# expansion_board.net
KiCad netlist of a schematic drawn in EAGLE
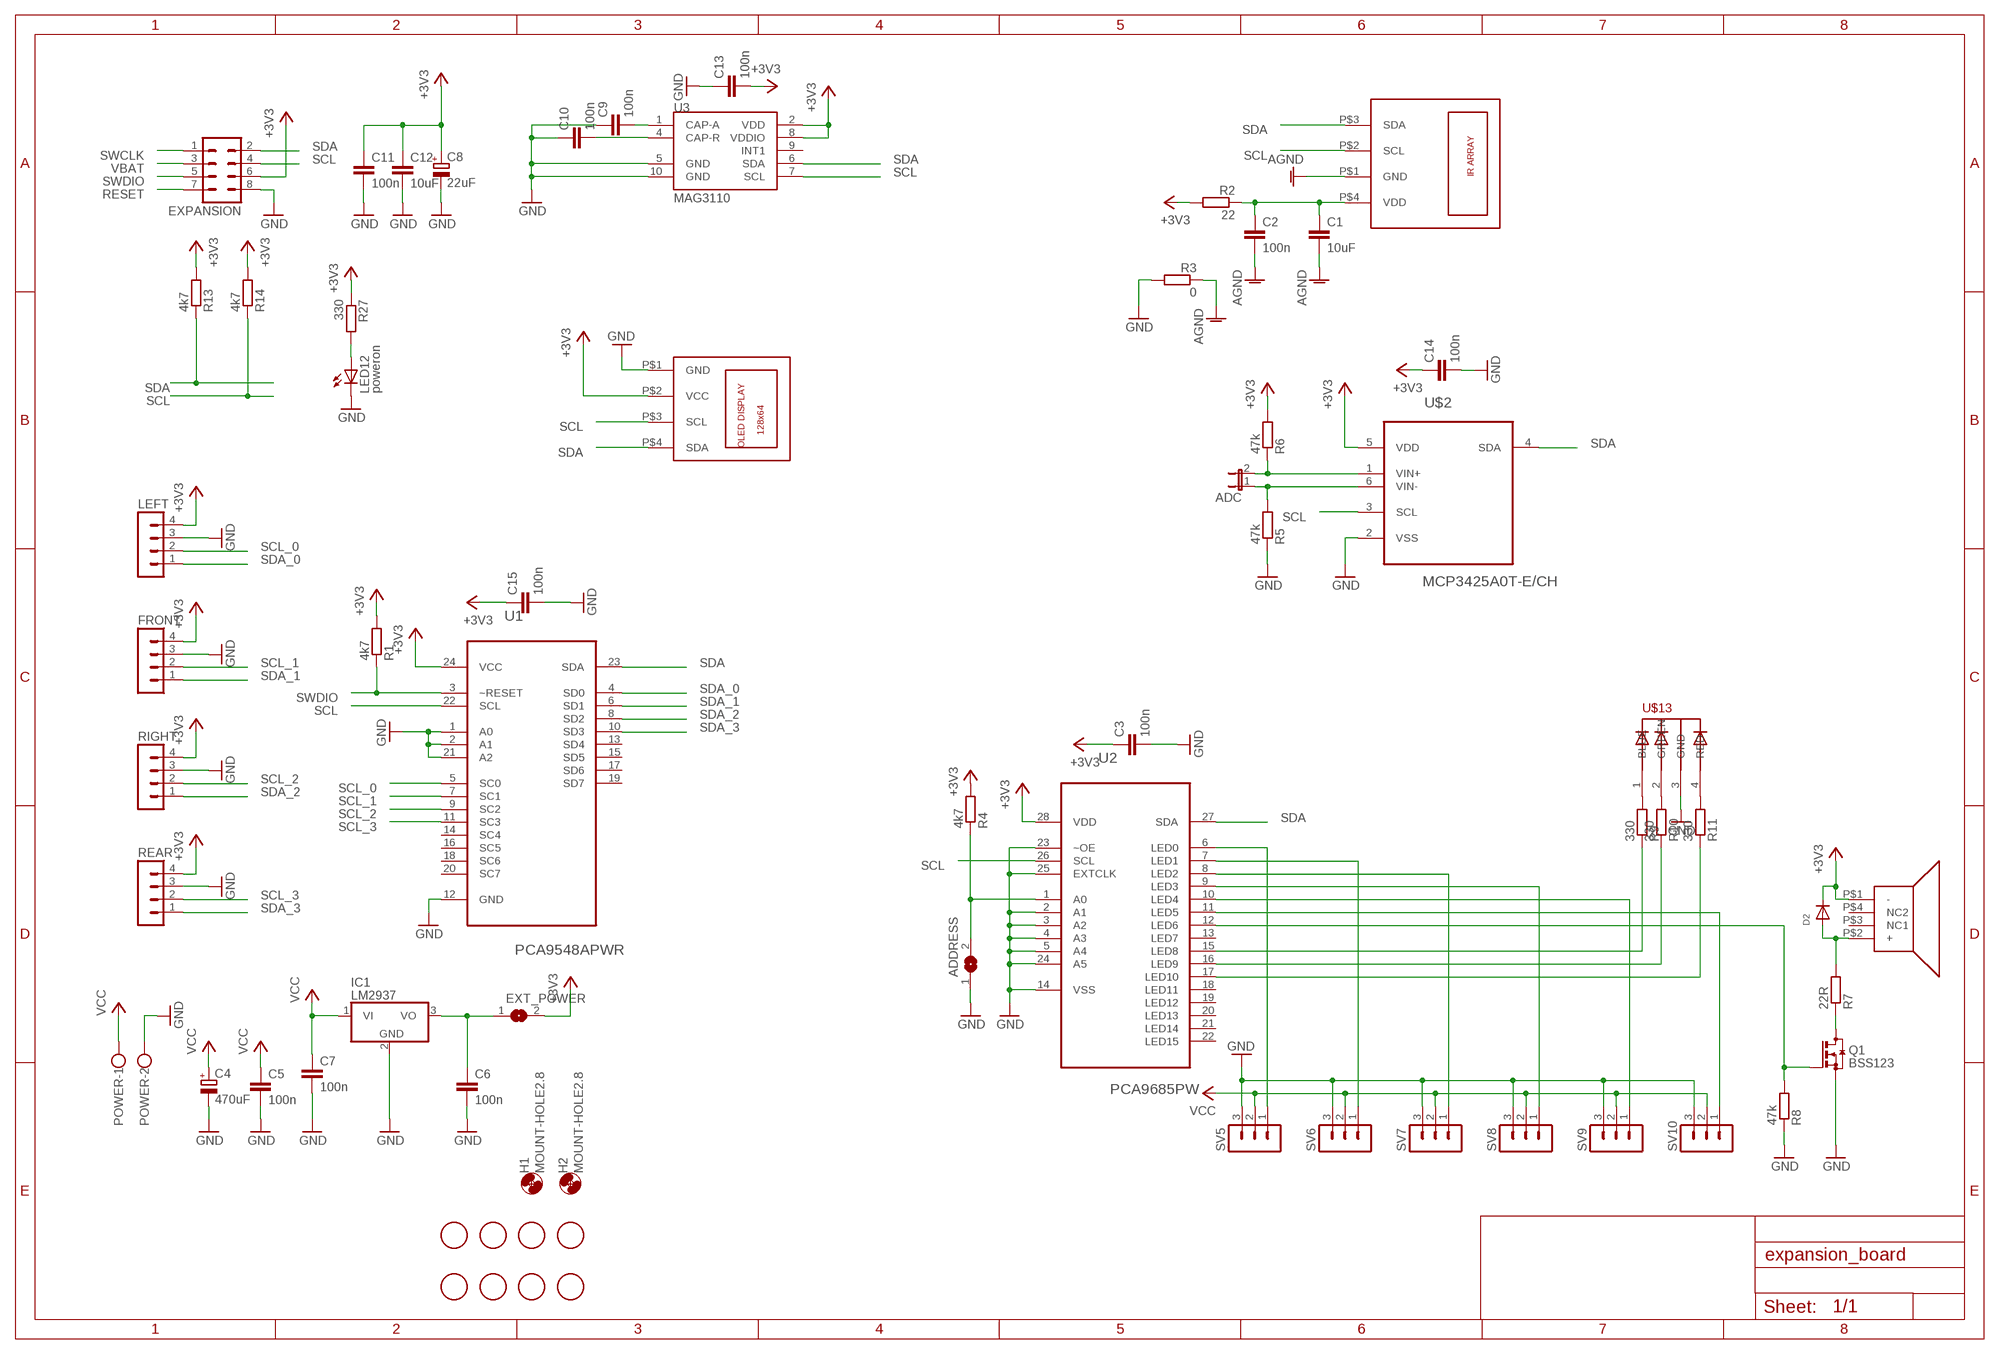
[diagram p0: schematic, sheet 1]

(export (version "E")
  (design (tool "Eeschema 10.0.6"))
  (components
    (comp (ref "ADC")
      (value "JP1E")
      (footprint "eagle-import:JP1")
      (libsource (lib "eagle-import") (part "JP1E"))
    )
    (comp (ref "ADDRESS")
      (value "SJ")
      (footprint "eagle-import:SJ")
      (libsource (lib "eagle-import") (part "SJ"))
    )
    (comp (ref "C1")
      (value "10uF")
      (footprint "eagle-import:C0805")
      (libsource (lib "eagle-import") (part "C-EUC0805"))
    )
    (comp (ref "C2")
      (value "100n")
      (footprint "eagle-import:C0805")
      (libsource (lib "eagle-import") (part "C-EUC0805"))
    )
    (comp (ref "C3")
      (value "100n")
      (footprint "eagle-import:C0805")
      (libsource (lib "eagle-import") (part "C-EUC0805"))
    )
    (comp (ref "C4")
      (value "470uF")
      (footprint "eagle-import:153CLV-1012")
      (libsource (lib "eagle-import") (part "CPOL-EU153CLV-1012"))
    )
    (comp (ref "C5")
      (value "100n")
      (footprint "eagle-import:C0805")
      (libsource (lib "eagle-import") (part "C-EUC0805"))
    )
    (comp (ref "C6")
      (value "100n")
      (footprint "eagle-import:C0805")
      (libsource (lib "eagle-import") (part "C-EUC0805"))
    )
    (comp (ref "C7")
      (value "100n")
      (footprint "eagle-import:C0805")
      (libsource (lib "eagle-import") (part "C-EUC0805"))
    )
    (comp (ref "C8")
      (value "22uF")
      (footprint "eagle-import:153CLV-0505")
      (libsource (lib "eagle-import") (part "CPOL-EU153CLV-0505"))
    )
    (comp (ref "C9")
      (value "100n")
      (footprint "eagle-import:C0805")
      (libsource (lib "eagle-import") (part "C-EUC0805"))
    )
    (comp (ref "C10")
      (value "100n")
      (footprint "eagle-import:C0805")
      (libsource (lib "eagle-import") (part "C-EUC0805"))
    )
    (comp (ref "C11")
      (value "100n")
      (footprint "eagle-import:C0805")
      (libsource (lib "eagle-import") (part "C-EUC0805"))
    )
    (comp (ref "C12")
      (value "10uF")
      (footprint "eagle-import:C0805")
      (libsource (lib "eagle-import") (part "C-EUC0805"))
    )
    (comp (ref "C13")
      (value "100n")
      (footprint "eagle-import:C0805")
      (libsource (lib "eagle-import") (part "C-EUC0805"))
    )
    (comp (ref "C14")
      (value "100n")
      (footprint "eagle-import:C0805")
      (libsource (lib "eagle-import") (part "C-EUC0805"))
    )
    (comp (ref "C15")
      (value "100n")
      (footprint "eagle-import:C0805")
      (libsource (lib "eagle-import") (part "C-EUC0805"))
    )
    (comp (ref "D2")
      (value "DIODE_SOD-123FL")
      (footprint "eagle-import:SOD-123FL")
      (libsource (lib "eagle-import") (part "DIODE_SOD-123FL"))
    )
    (comp (ref "EXPANSION")
      (value "MA04-2")
      (footprint "eagle-import:MA04-2")
      (libsource (lib "eagle-import") (part "MA04-2"))
    )
    (comp (ref "EXT_POWER")
      (value "SJ")
      (footprint "eagle-import:SJ")
      (libsource (lib "eagle-import") (part "SJ"))
    )
    (comp (ref "FRONT")
      (value "MA04-1")
      (footprint "eagle-import:MA04-1")
      (libsource (lib "eagle-import") (part "MA04-1"))
    )
    (comp (ref "H1")
      (value "MOUNT-HOLE2.8")
      (footprint "eagle-import:2,8")
      (libsource (lib "eagle-import") (part "MOUNT-HOLE2.8"))
    )
    (comp (ref "H2")
      (value "MOUNT-HOLE2.8")
      (footprint "eagle-import:2,8")
      (libsource (lib "eagle-import") (part "MOUNT-HOLE2.8"))
    )
    (comp (ref "IC1")
      (value "LM2937")
      (footprint "eagle-import:TO263-3")
      (libsource (lib "eagle-import") (part "LM2937"))
    )
    (comp (ref "LED12")
      (value "poweron")
      (footprint "eagle-import:CHIPLED_1206")
      (libsource (lib "eagle-import") (part "LEDCHIPLED_1206"))
    )
    (comp (ref "LEFT")
      (value "MA04-1")
      (footprint "eagle-import:MA04-1")
      (libsource (lib "eagle-import") (part "MA04-1"))
    )
    (comp (ref "POWER")
      (value "W237-102")
      (footprint "eagle-import:W237-102")
      (fields (field (name "MPN") "237-102"))
      (libsource (lib "eagle-import") (part "W237-102"))
    )
    (comp (ref "Q1")
      (value "BSS123")
      (footprint "eagle-import:SOT23")
      (libsource (lib "eagle-import") (part "BSS123"))
    )
    (comp (ref "R1")
      (value "4k7")
      (footprint "eagle-import:M0805")
      (libsource (lib "eagle-import") (part "R-EU_M0805"))
    )
    (comp (ref "R2")
      (value "22")
      (footprint "eagle-import:M0805")
      (libsource (lib "eagle-import") (part "R-EU_M0805"))
    )
    (comp (ref "R3")
      (value "0")
      (footprint "eagle-import:M0805")
      (libsource (lib "eagle-import") (part "R-EU_M0805"))
    )
    (comp (ref "R4")
      (value "4k7")
      (footprint "eagle-import:M0805")
      (libsource (lib "eagle-import") (part "R-EU_M0805"))
    )
    (comp (ref "R5")
      (value "47k")
      (footprint "eagle-import:M0805")
      (libsource (lib "eagle-import") (part "R-EU_M0805"))
    )
    (comp (ref "R6")
      (value "47k")
      (footprint "eagle-import:M0805")
      (libsource (lib "eagle-import") (part "R-EU_M0805"))
    )
    (comp (ref "R7")
      (value "22R")
      (footprint "eagle-import:M0805")
      (libsource (lib "eagle-import") (part "R-EU_M0805"))
    )
    (comp (ref "R8")
      (value "47k")
      (footprint "eagle-import:M0805")
      (libsource (lib "eagle-import") (part "R-EU_M0805"))
    )
    (comp (ref "R9")
      (value "330")
      (footprint "eagle-import:M0805")
      (libsource (lib "eagle-import") (part "R-EU_M0805"))
    )
    (comp (ref "R10")
      (value "330")
      (footprint "eagle-import:M0805")
      (libsource (lib "eagle-import") (part "R-EU_M0805"))
    )
    (comp (ref "R11")
      (value "330")
      (footprint "eagle-import:M0805")
      (libsource (lib "eagle-import") (part "R-EU_M0805"))
    )
    (comp (ref "R13")
      (value "4k7")
      (footprint "eagle-import:M0805")
      (libsource (lib "eagle-import") (part "R-EU_M0805"))
    )
    (comp (ref "R14")
      (value "4k7")
      (footprint "eagle-import:M0805")
      (libsource (lib "eagle-import") (part "R-EU_M0805"))
    )
    (comp (ref "R27")
      (value "330")
      (footprint "eagle-import:M0805")
      (libsource (lib "eagle-import") (part "R-EU_M0805"))
    )
    (comp (ref "REAR")
      (value "MA04-1")
      (footprint "eagle-import:MA04-1")
      (libsource (lib "eagle-import") (part "MA04-1"))
    )
    (comp (ref "RIGHT")
      (value "MA04-1")
      (footprint "eagle-import:MA04-1")
      (libsource (lib "eagle-import") (part "MA04-1"))
    )
    (comp (ref "SV5")
      (value "MA03-1")
      (footprint "eagle-import:MA03-1")
      (libsource (lib "eagle-import") (part "MA03-1"))
    )
    (comp (ref "SV6")
      (value "MA03-1")
      (footprint "eagle-import:MA03-1")
      (libsource (lib "eagle-import") (part "MA03-1"))
    )
    (comp (ref "SV7")
      (value "MA03-1")
      (footprint "eagle-import:MA03-1")
      (libsource (lib "eagle-import") (part "MA03-1"))
    )
    (comp (ref "SV8")
      (value "MA03-1")
      (footprint "eagle-import:MA03-1")
      (libsource (lib "eagle-import") (part "MA03-1"))
    )
    (comp (ref "SV9")
      (value "MA03-1")
      (footprint "eagle-import:MA03-1")
      (libsource (lib "eagle-import") (part "MA03-1"))
    )
    (comp (ref "SV10")
      (value "MA03-1")
      (footprint "eagle-import:MA03-1")
      (libsource (lib "eagle-import") (part "MA03-1"))
    )
    (comp (ref "U$1")
      (value "MLX90621")
      (footprint "eagle-import:MLX90621")
      (libsource (lib "eagle-import") (part "MLX90621"))
    )
    (comp (ref "U$2")
      (value "MCP3425A0T-E/CH")
      (footprint "eagle-import:SOT95P270X145-6N")
      (libsource (lib "eagle-import") (part "MCP3425A0T-E/CH"))
    )
    (comp (ref "U$3")
      (value "SPEAKER_KAAG15008C")
      (footprint "eagle-import:KAAG15008C")
      (libsource (lib "eagle-import") (part "SPEAKER_KAAG15008C"))
    )
    (comp (ref "U$4")
      (value "OLED_DISPLAY_096_INCH")
      (footprint "eagle-import:OLED_DISPLAY_096_INCH")
      (libsource (lib "eagle-import") (part "OLED_DISPLAY_096_INCH"))
    )
    (comp (ref "U$5")
      (value "FIDUCIAL")
      (footprint "eagle-import:FIDUCIAL_1MM")
      (libsource (lib "eagle-import") (part "FIDUCIAL"))
    )
    (comp (ref "U$6")
      (value "FIDUCIAL")
      (footprint "eagle-import:FIDUCIAL_1MM")
      (libsource (lib "eagle-import") (part "FIDUCIAL"))
    )
    (comp (ref "U$7")
      (value "FIDUCIAL")
      (footprint "eagle-import:FIDUCIAL_1MM")
      (libsource (lib "eagle-import") (part "FIDUCIAL"))
    )
    (comp (ref "U$8")
      (value "FIDUCIAL")
      (footprint "eagle-import:FIDUCIAL_1MM")
      (libsource (lib "eagle-import") (part "FIDUCIAL"))
    )
    (comp (ref "U$9")
      (value "FIDUCIAL")
      (footprint "eagle-import:FIDUCIAL_1MM")
      (libsource (lib "eagle-import") (part "FIDUCIAL"))
    )
    (comp (ref "U$10")
      (value "FIDUCIAL")
      (footprint "eagle-import:FIDUCIAL_1MM")
      (libsource (lib "eagle-import") (part "FIDUCIAL"))
    )
    (comp (ref "U$11")
      (value "FIDUCIAL")
      (footprint "eagle-import:FIDUCIAL_1MM")
      (libsource (lib "eagle-import") (part "FIDUCIAL"))
    )
    (comp (ref "U$12")
      (value "FIDUCIAL")
      (footprint "eagle-import:FIDUCIAL_1MM")
      (libsource (lib "eagle-import") (part "FIDUCIAL"))
    )
    (comp (ref "U$13")
      (value "5MMRGBLED")
      (footprint "eagle-import:LED5MMRGB")
      (libsource (lib "eagle-import") (part "5MMRGBLED"))
    )
    (comp (ref "U1")
      (value "PCA9548APWR")
      (footprint "eagle-import:SOP65P640X120-24N")
      (fields (field (name "MPN") "PCA9548APWR    False"))
      (libsource (lib "eagle-import") (part "PCA9548APWR"))
    )
    (comp (ref "U2")
      (value "PCA9685PW")
      (footprint "eagle-import:SOP65P640X110-28N")
      (libsource (lib "eagle-import") (part "PCA9685PW"))
    )
    (comp (ref "U3")
      (value "MAG3110")
      (footprint "eagle-import:DFN-10")
      (libsource (lib "eagle-import") (part "MAG3110"))
    )
  )
  (nets
    (net (code "1") (name "+3V3") (class "Default")
      (node (ref "C11") (pin "1") (pinfunction "1_1") (pintype "passive"))
      (node (ref "C12") (pin "1") (pinfunction "1_1") (pintype "passive"))
      (node (ref "C13") (pin "2") (pinfunction "2_2") (pintype "passive"))
      (node (ref "C14") (pin "1") (pinfunction "1_1") (pintype "passive"))
      (node (ref "C15") (pin "1") (pinfunction "1_1") (pintype "passive"))
      (node (ref "C3") (pin "1") (pinfunction "1_1") (pintype "passive"))
      (node (ref "C8") (pin "+") (pinfunction "+_+") (pintype "passive"))
      (node (ref "D2") (pin "C") (pinfunction "C_C") (pintype "passive"))
      (node (ref "EXPANSION") (pin "6") (pinfunction "6_6") (pintype "passive"))
      (node (ref "EXT_POWER") (pin "2") (pinfunction "2_2") (pintype "passive"))
      (node (ref "FRONT") (pin "4") (pinfunction "4_4") (pintype "passive"))
      (node (ref "LEFT") (pin "4") (pinfunction "4_4") (pintype "passive"))
      (node (ref "R1") (pin "2") (pinfunction "2_2") (pintype "passive"))
      (node (ref "R13") (pin "2") (pinfunction "2_2") (pintype "passive"))
      (node (ref "R14") (pin "2") (pinfunction "2_2") (pintype "passive"))
      (node (ref "R2") (pin "2") (pinfunction "2_2") (pintype "passive"))
      (node (ref "R27") (pin "1") (pinfunction "1_1") (pintype "passive"))
      (node (ref "R4") (pin "2") (pinfunction "2_2") (pintype "passive"))
      (node (ref "R6") (pin "2") (pinfunction "2_2") (pintype "passive"))
      (node (ref "REAR") (pin "4") (pinfunction "4_4") (pintype "passive"))
      (node (ref "RIGHT") (pin "4") (pinfunction "4_4") (pintype "passive"))
      (node (ref "U$2") (pin "5") (pinfunction "VDD_5") (pintype "power_in"))
      (node (ref "U$3") (pin "P$1") (pinfunction "-_P$1") (pintype "bidirectional"))
      (node (ref "U$4") (pin "P$2") (pinfunction "VCC_P$2") (pintype "bidirectional"))
      (node (ref "U1") (pin "24") (pinfunction "VCC_24") (pintype "power_in"))
      (node (ref "U2") (pin "28") (pinfunction "VDD_28") (pintype "power_in"))
      (node (ref "U3") (pin "2") (pinfunction "VDD_2") (pintype "bidirectional"))
      (node (ref "U3") (pin "8") (pinfunction "VDDIO_8") (pintype "bidirectional"))
    )
    (net (code "2") (name "/RESET") (class "Default")
      (node (ref "EXPANSION") (pin "7") (pinfunction "7_7") (pintype "passive"))
    )
    (net (code "3") (name "/SCL") (class "Default")
      (node (ref "EXPANSION") (pin "4") (pinfunction "4_4") (pintype "passive"))
      (node (ref "R14") (pin "1") (pinfunction "1_1") (pintype "passive"))
      (node (ref "U$1") (pin "P$2") (pinfunction "SCL_P$2") (pintype "bidirectional"))
      (node (ref "U$2") (pin "3") (pinfunction "SCL_3") (pintype "input"))
      (node (ref "U$4") (pin "P$3") (pinfunction "SCL_P$3") (pintype "bidirectional"))
      (node (ref "U1") (pin "22") (pinfunction "SCL_22") (pintype "input"))
      (node (ref "U2") (pin "26") (pinfunction "SCL_26") (pintype "input"))
      (node (ref "U3") (pin "7") (pinfunction "SCL_7") (pintype "bidirectional"))
    )
    (net (code "4") (name "/SCL_0") (class "Default")
      (node (ref "LEFT") (pin "2") (pinfunction "2_2") (pintype "passive"))
      (node (ref "U1") (pin "5") (pinfunction "SC0_5") (pintype "bidirectional"))
    )
    (net (code "5") (name "/SCL_1") (class "Default")
      (node (ref "FRONT") (pin "2") (pinfunction "2_2") (pintype "passive"))
      (node (ref "U1") (pin "7") (pinfunction "SC1_7") (pintype "bidirectional"))
    )
    (net (code "6") (name "/SCL_2") (class "Default")
      (node (ref "RIGHT") (pin "2") (pinfunction "2_2") (pintype "passive"))
      (node (ref "U1") (pin "9") (pinfunction "SC2_9") (pintype "bidirectional"))
    )
    (net (code "7") (name "/SCL_3") (class "Default")
      (node (ref "REAR") (pin "2") (pinfunction "2_2") (pintype "passive"))
      (node (ref "U1") (pin "11") (pinfunction "SC3_11") (pintype "bidirectional"))
    )
    (net (code "8") (name "/SDA") (class "Default")
      (node (ref "EXPANSION") (pin "2") (pinfunction "2_2") (pintype "passive"))
      (node (ref "R13") (pin "1") (pinfunction "1_1") (pintype "passive"))
      (node (ref "U$1") (pin "P$3") (pinfunction "SDA_P$3") (pintype "bidirectional"))
      (node (ref "U$2") (pin "4") (pinfunction "SDA_4") (pintype "bidirectional"))
      (node (ref "U$4") (pin "P$4") (pinfunction "SDA_P$4") (pintype "bidirectional"))
      (node (ref "U1") (pin "23") (pinfunction "SDA_23") (pintype "bidirectional"))
      (node (ref "U2") (pin "27") (pinfunction "SDA_27") (pintype "bidirectional"))
      (node (ref "U3") (pin "6") (pinfunction "SDA_6") (pintype "bidirectional"))
    )
    (net (code "9") (name "/SDA_0") (class "Default")
      (node (ref "LEFT") (pin "1") (pinfunction "1_1") (pintype "passive"))
      (node (ref "U1") (pin "4") (pinfunction "SD0_4") (pintype "bidirectional"))
    )
    (net (code "10") (name "/SDA_1") (class "Default")
      (node (ref "FRONT") (pin "1") (pinfunction "1_1") (pintype "passive"))
      (node (ref "U1") (pin "6") (pinfunction "SD1_6") (pintype "bidirectional"))
    )
    (net (code "11") (name "/SDA_2") (class "Default")
      (node (ref "RIGHT") (pin "1") (pinfunction "1_1") (pintype "passive"))
      (node (ref "U1") (pin "8") (pinfunction "SD2_8") (pintype "bidirectional"))
    )
    (net (code "12") (name "/SDA_3") (class "Default")
      (node (ref "REAR") (pin "1") (pinfunction "1_1") (pintype "passive"))
      (node (ref "U1") (pin "10") (pinfunction "SD3_10") (pintype "bidirectional"))
    )
    (net (code "13") (name "/SWCLK") (class "Default")
      (node (ref "EXPANSION") (pin "1") (pinfunction "1_1") (pintype "passive"))
    )
    (net (code "14") (name "/SWDIO") (class "Default")
      (node (ref "EXPANSION") (pin "5") (pinfunction "5_5") (pintype "passive"))
      (node (ref "R1") (pin "1") (pinfunction "1_1") (pintype "passive"))
      (node (ref "U1") (pin "3") (pinfunction "~{RESET}_3") (pintype "input"))
    )
    (net (code "15") (name "/VBAT") (class "Default")
      (node (ref "EXPANSION") (pin "3") (pinfunction "3_3") (pintype "passive"))
    )
    (net (code "16") (name "AGND") (class "Default")
      (node (ref "C1") (pin "2") (pinfunction "2_2") (pintype "passive"))
      (node (ref "C2") (pin "2") (pinfunction "2_2") (pintype "passive"))
      (node (ref "R3") (pin "1") (pinfunction "1_1") (pintype "passive"))
      (node (ref "U$1") (pin "P$1") (pinfunction "GND_P$1") (pintype "bidirectional"))
    )
    (net (code "17") (name "GND") (class "Default")
      (node (ref "ADDRESS") (pin "1") (pinfunction "1_1") (pintype "passive"))
      (node (ref "C10") (pin "1") (pinfunction "1_1") (pintype "passive"))
      (node (ref "C11") (pin "2") (pinfunction "2_2") (pintype "passive"))
      (node (ref "C12") (pin "2") (pinfunction "2_2") (pintype "passive"))
      (node (ref "C13") (pin "1") (pinfunction "1_1") (pintype "passive"))
      (node (ref "C14") (pin "2") (pinfunction "2_2") (pintype "passive"))
      (node (ref "C15") (pin "2") (pinfunction "2_2") (pintype "passive"))
      (node (ref "C3") (pin "2") (pinfunction "2_2") (pintype "passive"))
      (node (ref "C4") (pin "-") (pinfunction "-_-") (pintype "passive"))
      (node (ref "C5") (pin "2") (pinfunction "2_2") (pintype "passive"))
      (node (ref "C6") (pin "2") (pinfunction "2_2") (pintype "passive"))
      (node (ref "C7") (pin "2") (pinfunction "2_2") (pintype "passive"))
      (node (ref "C8") (pin "-") (pinfunction "-_-") (pintype "passive"))
      (node (ref "C9") (pin "1") (pinfunction "1_1") (pintype "passive"))
      (node (ref "EXPANSION") (pin "8") (pinfunction "8_8") (pintype "passive"))
      (node (ref "FRONT") (pin "3") (pinfunction "3_3") (pintype "passive"))
      (node (ref "IC1") (pin "2") (pinfunction "GND_2") (pintype "passive"))
      (node (ref "LED12") (pin "C") (pinfunction "C_C") (pintype "passive"))
      (node (ref "LEFT") (pin "3") (pinfunction "3_3") (pintype "passive"))
      (node (ref "POWER") (pin "2") (pinfunction "KL_2") (pintype "passive"))
      (node (ref "Q1") (pin "2") (pinfunction "S_2") (pintype "passive"))
      (node (ref "R3") (pin "2") (pinfunction "2_2") (pintype "passive"))
      (node (ref "R5") (pin "1") (pinfunction "1_1") (pintype "passive"))
      (node (ref "R8") (pin "1") (pinfunction "1_1") (pintype "passive"))
      (node (ref "REAR") (pin "3") (pinfunction "3_3") (pintype "passive"))
      (node (ref "RIGHT") (pin "3") (pinfunction "3_3") (pintype "passive"))
      (node (ref "SV10") (pin "3") (pinfunction "3_3") (pintype "passive"))
      (node (ref "SV5") (pin "3") (pinfunction "3_3") (pintype "passive"))
      (node (ref "SV6") (pin "3") (pinfunction "3_3") (pintype "passive"))
      (node (ref "SV7") (pin "3") (pinfunction "3_3") (pintype "passive"))
      (node (ref "SV8") (pin "3") (pinfunction "3_3") (pintype "passive"))
      (node (ref "SV9") (pin "3") (pinfunction "3_3") (pintype "passive"))
      (node (ref "U$13") (pin "3") (pinfunction "GND_3") (pintype "bidirectional"))
      (node (ref "U$2") (pin "2") (pinfunction "VSS_2") (pintype "passive"))
      (node (ref "U$4") (pin "P$1") (pinfunction "GND_P$1") (pintype "bidirectional"))
      (node (ref "U1") (pin "1") (pinfunction "A0_1") (pintype "input"))
      (node (ref "U1") (pin "12") (pinfunction "GND_12") (pintype "passive"))
      (node (ref "U1") (pin "2") (pinfunction "A1_2") (pintype "input"))
      (node (ref "U1") (pin "21") (pinfunction "A2_21") (pintype "input"))
      (node (ref "U2") (pin "14") (pinfunction "VSS_14") (pintype "passive"))
      (node (ref "U2") (pin "2") (pinfunction "A1_2") (pintype "input"))
      (node (ref "U2") (pin "23") (pinfunction "~{OE}_23") (pintype "input"))
      (node (ref "U2") (pin "24") (pinfunction "A5_24") (pintype "input"))
      (node (ref "U2") (pin "25") (pinfunction "EXTCLK_25") (pintype "input"))
      (node (ref "U2") (pin "3") (pinfunction "A2_3") (pintype "input"))
      (node (ref "U2") (pin "4") (pinfunction "A3_4") (pintype "input"))
      (node (ref "U2") (pin "5") (pinfunction "A4_5") (pintype "input"))
      (node (ref "U3") (pin "10") (pinfunction "GND_10") (pintype "bidirectional"))
      (node (ref "U3") (pin "5") (pinfunction "GND_5") (pintype "bidirectional"))
    )
    (net (code "18") (name "Net-(IC1-VO)") (class "Default")
      (node (ref "C6") (pin "1") (pinfunction "1_1") (pintype "passive"))
      (node (ref "EXT_POWER") (pin "1") (pinfunction "1_1") (pintype "passive"))
      (node (ref "IC1") (pin "3") (pinfunction "VO_3") (pintype "passive"))
    )
    (net (code "19") (name "Net-(LED12-PadA)") (class "Default")
      (node (ref "LED12") (pin "A") (pinfunction "A_A") (pintype "passive"))
      (node (ref "R27") (pin "2") (pinfunction "2_2") (pintype "passive"))
    )
    (net (code "20") (name "Net-(Q1-D)") (class "Default")
      (node (ref "Q1") (pin "3") (pinfunction "D_3") (pintype "passive"))
      (node (ref "R7") (pin "1") (pinfunction "1_1") (pintype "passive"))
    )
    (net (code "21") (name "Net-(Q1-G)") (class "Default")
      (node (ref "Q1") (pin "1") (pinfunction "G_1") (pintype "passive"))
      (node (ref "R8") (pin "2") (pinfunction "2_2") (pintype "passive"))
      (node (ref "U2") (pin "12") (pinfunction "LED6_12") (pintype "output"))
    )
    (net (code "22") (name "Net-(U$1-VDD)") (class "Default")
      (node (ref "C1") (pin "1") (pinfunction "1_1") (pintype "passive"))
      (node (ref "C2") (pin "1") (pinfunction "1_1") (pintype "passive"))
      (node (ref "R2") (pin "1") (pinfunction "1_1") (pintype "passive"))
      (node (ref "U$1") (pin "P$4") (pinfunction "VDD_P$4") (pintype "bidirectional"))
    )
    (net (code "23") (name "Net-(U$2-VIN+)") (class "Default")
      (node (ref "ADC") (pin "2") (pinfunction "2_2") (pintype "passive"))
      (node (ref "R6") (pin "1") (pinfunction "1_1") (pintype "passive"))
      (node (ref "U$2") (pin "1") (pinfunction "VIN+_1") (pintype "input"))
    )
    (net (code "24") (name "Net-(U$2-VIN-)") (class "Default")
      (node (ref "ADC") (pin "1") (pinfunction "1_1") (pintype "passive"))
      (node (ref "R5") (pin "2") (pinfunction "2_2") (pintype "passive"))
      (node (ref "U$2") (pin "6") (pinfunction "VIN-_6") (pintype "input"))
    )
    (net (code "25") (name "Net-(U$3-+)") (class "Default")
      (node (ref "D2") (pin "A") (pinfunction "A_A") (pintype "passive"))
      (node (ref "R7") (pin "2") (pinfunction "2_2") (pintype "passive"))
      (node (ref "U$3") (pin "P$2") (pinfunction "+_P$2") (pintype "bidirectional"))
    )
    (net (code "26") (name "Net-(U$13-BLUE)") (class "Default")
      (node (ref "R9") (pin "2") (pinfunction "2_2") (pintype "passive"))
      (node (ref "U$13") (pin "1") (pinfunction "BLUE_1") (pintype "bidirectional"))
    )
    (net (code "27") (name "Net-(U$13-GREEN)") (class "Default")
      (node (ref "R10") (pin "2") (pinfunction "2_2") (pintype "passive"))
      (node (ref "U$13") (pin "2") (pinfunction "GREEN_2") (pintype "bidirectional"))
    )
    (net (code "28") (name "Net-(U$13-RED)") (class "Default")
      (node (ref "R11") (pin "2") (pinfunction "2_2") (pintype "passive"))
      (node (ref "U$13") (pin "4") (pinfunction "RED_4") (pintype "bidirectional"))
    )
    (net (code "29") (name "Net-(U2-A0)") (class "Default")
      (node (ref "ADDRESS") (pin "2") (pinfunction "2_2") (pintype "passive"))
      (node (ref "R4") (pin "1") (pinfunction "1_1") (pintype "passive"))
      (node (ref "U2") (pin "1") (pinfunction "A0_1") (pintype "input"))
    )
    (net (code "30") (name "Net-(U2-LED0)") (class "Default")
      (node (ref "SV5") (pin "1") (pinfunction "1_1") (pintype "passive"))
      (node (ref "U2") (pin "6") (pinfunction "LED0_6") (pintype "output"))
    )
    (net (code "31") (name "Net-(U2-LED1)") (class "Default")
      (node (ref "SV6") (pin "1") (pinfunction "1_1") (pintype "passive"))
      (node (ref "U2") (pin "7") (pinfunction "LED1_7") (pintype "output"))
    )
    (net (code "32") (name "Net-(U2-LED2)") (class "Default")
      (node (ref "SV7") (pin "1") (pinfunction "1_1") (pintype "passive"))
      (node (ref "U2") (pin "8") (pinfunction "LED2_8") (pintype "output"))
    )
    (net (code "33") (name "Net-(U2-LED3)") (class "Default")
      (node (ref "SV8") (pin "1") (pinfunction "1_1") (pintype "passive"))
      (node (ref "U2") (pin "9") (pinfunction "LED3_9") (pintype "output"))
    )
    (net (code "34") (name "Net-(U2-LED4)") (class "Default")
      (node (ref "SV9") (pin "1") (pinfunction "1_1") (pintype "passive"))
      (node (ref "U2") (pin "10") (pinfunction "LED4_10") (pintype "output"))
    )
    (net (code "35") (name "Net-(U2-LED5)") (class "Default")
      (node (ref "SV10") (pin "1") (pinfunction "1_1") (pintype "passive"))
      (node (ref "U2") (pin "11") (pinfunction "LED5_11") (pintype "output"))
    )
    (net (code "36") (name "Net-(U2-LED8)") (class "Default")
      (node (ref "R9") (pin "1") (pinfunction "1_1") (pintype "passive"))
      (node (ref "U2") (pin "15") (pinfunction "LED8_15") (pintype "output"))
    )
    (net (code "37") (name "Net-(U2-LED9)") (class "Default")
      (node (ref "R10") (pin "1") (pinfunction "1_1") (pintype "passive"))
      (node (ref "U2") (pin "16") (pinfunction "LED9_16") (pintype "output"))
    )
    (net (code "38") (name "Net-(U2-LED10)") (class "Default")
      (node (ref "R11") (pin "1") (pinfunction "1_1") (pintype "passive"))
      (node (ref "U2") (pin "17") (pinfunction "LED10_17") (pintype "output"))
    )
    (net (code "39") (name "Net-(U3-CAP-A)") (class "Default")
      (node (ref "C9") (pin "2") (pinfunction "2_2") (pintype "passive"))
      (node (ref "U3") (pin "1") (pinfunction "CAP-A_1") (pintype "bidirectional"))
    )
    (net (code "40") (name "Net-(U3-CAP-R)") (class "Default")
      (node (ref "C10") (pin "2") (pinfunction "2_2") (pintype "passive"))
      (node (ref "U3") (pin "4") (pinfunction "CAP-R_4") (pintype "bidirectional"))
    )
    (net (code "41") (name "VCC") (class "Default")
      (node (ref "C4") (pin "+") (pinfunction "+_+") (pintype "passive"))
      (node (ref "C5") (pin "1") (pinfunction "1_1") (pintype "passive"))
      (node (ref "C7") (pin "1") (pinfunction "1_1") (pintype "passive"))
      (node (ref "IC1") (pin "1") (pinfunction "VI_1") (pintype "input"))
      (node (ref "POWER") (pin "1") (pinfunction "KL_1") (pintype "passive"))
      (node (ref "SV10") (pin "2") (pinfunction "2_2") (pintype "passive"))
      (node (ref "SV5") (pin "2") (pinfunction "2_2") (pintype "passive"))
      (node (ref "SV6") (pin "2") (pinfunction "2_2") (pintype "passive"))
      (node (ref "SV7") (pin "2") (pinfunction "2_2") (pintype "passive"))
      (node (ref "SV8") (pin "2") (pinfunction "2_2") (pintype "passive"))
      (node (ref "SV9") (pin "2") (pinfunction "2_2") (pintype "passive"))
    )
    (net (code "42") (name "unconnected-(U$3-NC1-PadP$3)") (class "Default")
      (node (ref "U$3") (pin "P$3") (pinfunction "NC1_P$3") (pintype "bidirectional"))
    )
    (net (code "43") (name "unconnected-(U$3-NC2-PadP$4)") (class "Default")
      (node (ref "U$3") (pin "P$4") (pinfunction "NC2_P$4") (pintype "bidirectional"))
    )
    (net (code "44") (name "unconnected-(U1-SC4-Pad14)") (class "Default")
      (node (ref "U1") (pin "14") (pinfunction "SC4_14") (pintype "bidirectional"))
    )
    (net (code "45") (name "unconnected-(U1-SC5-Pad16)") (class "Default")
      (node (ref "U1") (pin "16") (pinfunction "SC5_16") (pintype "bidirectional"))
    )
    (net (code "46") (name "unconnected-(U1-SC6-Pad18)") (class "Default")
      (node (ref "U1") (pin "18") (pinfunction "SC6_18") (pintype "bidirectional"))
    )
    (net (code "47") (name "unconnected-(U1-SC7-Pad20)") (class "Default")
      (node (ref "U1") (pin "20") (pinfunction "SC7_20") (pintype "bidirectional"))
    )
    (net (code "48") (name "unconnected-(U1-SD4-Pad13)") (class "Default")
      (node (ref "U1") (pin "13") (pinfunction "SD4_13") (pintype "bidirectional"))
    )
    (net (code "49") (name "unconnected-(U1-SD5-Pad15)") (class "Default")
      (node (ref "U1") (pin "15") (pinfunction "SD5_15") (pintype "bidirectional"))
    )
    (net (code "50") (name "unconnected-(U1-SD6-Pad17)") (class "Default")
      (node (ref "U1") (pin "17") (pinfunction "SD6_17") (pintype "bidirectional"))
    )
    (net (code "51") (name "unconnected-(U1-SD7-Pad19)") (class "Default")
      (node (ref "U1") (pin "19") (pinfunction "SD7_19") (pintype "bidirectional"))
    )
    (net (code "52") (name "unconnected-(U2-LED7-Pad13)") (class "Default")
      (node (ref "U2") (pin "13") (pinfunction "LED7_13") (pintype "output"))
    )
    (net (code "53") (name "unconnected-(U2-LED11-Pad18)") (class "Default")
      (node (ref "U2") (pin "18") (pinfunction "LED11_18") (pintype "output"))
    )
    (net (code "54") (name "unconnected-(U2-LED12-Pad19)") (class "Default")
      (node (ref "U2") (pin "19") (pinfunction "LED12_19") (pintype "output"))
    )
    (net (code "55") (name "unconnected-(U2-LED13-Pad20)") (class "Default")
      (node (ref "U2") (pin "20") (pinfunction "LED13_20") (pintype "output"))
    )
    (net (code "56") (name "unconnected-(U2-LED14-Pad21)") (class "Default")
      (node (ref "U2") (pin "21") (pinfunction "LED14_21") (pintype "output"))
    )
    (net (code "57") (name "unconnected-(U2-LED15-Pad22)") (class "Default")
      (node (ref "U2") (pin "22") (pinfunction "LED15_22") (pintype "output"))
    )
    (net (code "58") (name "unconnected-(U3-INT1-Pad9)") (class "Default")
      (node (ref "U3") (pin "9") (pinfunction "INT1_9") (pintype "bidirectional"))
    )
  )
)
